# Fuente.net
KiCad netlist of a schematic drawn in Altium Designer
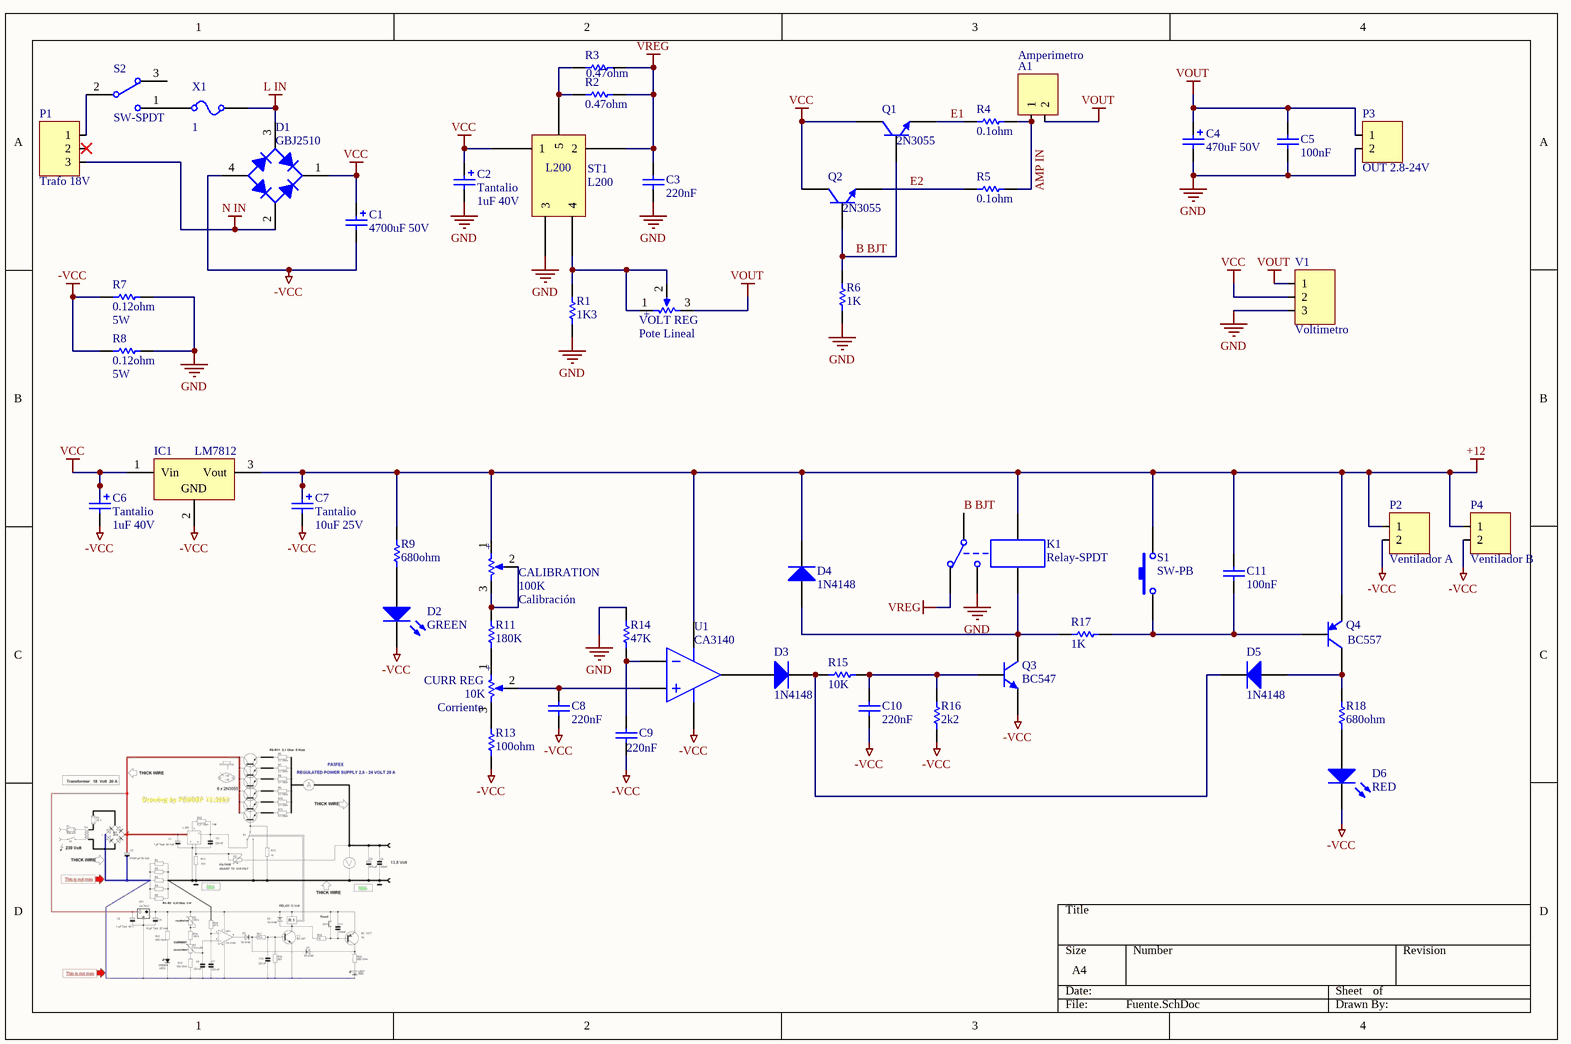
[diagram p0: Fuente.SchDoc]

(export (version "E")
  (design (tool "Eeschema 10.0.6"))
  (components
    (comp (ref "A1")
      (value "Amperimetro")
      (footprint "BORNERA 2")
      (description "Header, 2-Pin")
      (fields (field (name "PUBLISHER") "Altium Limited"))
      (libsource (lib "SchLibPutallaz") (part "Bornera"))
    )
    (comp (ref "C1")
      (value "4700uF 50V")
      (footprint "CAP 20MM")
      (description "Polarized Capacitor (Radial)")
      (fields (field (name "PUBLISHER") "Altium Limited"))
      (libsource (lib "SchLibPutallaz") (part "Cap Pol1"))
    )
    (comp (ref "C2")
      (value "Tantalio")
      (footprint "Cap Tantalio")
      (description "Polarized Capacitor (Radial)")
      (fields (field (name "ALTIUM_VALUE") "1uF 40V") (field (name "PUBLISHER") "Altium Limited"))
      (libsource (lib "SchLibPutallaz") (part "Cap Pol1"))
    )
    (comp (ref "C3")
      (value "220nF")
      (footprint "1206 res")
      (description "Capacitor")
      (fields (field (name "PUBLISHER") "Altium Limited"))
      (libsource (lib "SchLibPutallaz") (part "Cap"))
    )
    (comp (ref "C4")
      (value "470uF 50V")
      (footprint "CAP 10mm")
      (description "Polarized Capacitor (Radial)")
      (fields (field (name "PUBLISHER") "Altium Limited"))
      (libsource (lib "SchLibPutallaz") (part "Cap Pol1"))
    )
    (comp (ref "C5")
      (value "100nF")
      (footprint "0805 res")
      (description "Capacitor")
      (fields (field (name "PUBLISHER") "Altium Limited"))
      (libsource (lib "SchLibPutallaz") (part "Cap"))
    )
    (comp (ref "C6")
      (value "Tantalio")
      (footprint "Cap Tantalio")
      (description "Polarized Capacitor (Radial)")
      (fields (field (name "ALTIUM_VALUE") "1uF 40V") (field (name "PUBLISHER") "Altium Limited"))
      (libsource (lib "SchLibPutallaz") (part "Cap Pol1"))
    )
    (comp (ref "C7")
      (value "Tantalio")
      (footprint "Cap Tantalio")
      (description "Polarized Capacitor (Radial)")
      (fields (field (name "ALTIUM_VALUE") "10uF 25V") (field (name "PUBLISHER") "Altium Limited"))
      (libsource (lib "SchLibPutallaz") (part "Cap Pol1"))
    )
    (comp (ref "C8")
      (value "220nF")
      (footprint "1206 res")
      (description "Capacitor")
      (fields (field (name "PUBLISHER") "Altium Limited"))
      (libsource (lib "SchLibPutallaz") (part "Cap"))
    )
    (comp (ref "C9")
      (value "220nF")
      (footprint "1206 res")
      (description "Capacitor")
      (fields (field (name "PUBLISHER") "Altium Limited"))
      (libsource (lib "SchLibPutallaz") (part "Cap"))
    )
    (comp (ref "C10")
      (value "220nF")
      (footprint "1206 res")
      (description "Capacitor")
      (fields (field (name "PUBLISHER") "Altium Limited"))
      (libsource (lib "SchLibPutallaz") (part "Cap"))
    )
    (comp (ref "C11")
      (value "100nF")
      (footprint "0805 res")
      (description "Capacitor")
      (fields (field (name "PUBLISHER") "Altium Limited"))
      (libsource (lib "SchLibPutallaz") (part "Cap"))
    )
    (comp (ref "CALIBRATION")
      (value "100K")
      (footprint "Potenciometro")
      (libsource (lib "SchLibPutallaz") (part "Potenciometro"))
    )
    (comp (ref "CURR REG")
      (value "10K")
      (footprint "Potenciometro")
      (libsource (lib "SchLibPutallaz") (part "Potenciometro"))
    )
    (comp (ref "D1")
      (value "GBJ2510")
      (footprint "DIOB_GBJ2510")
      (description "Full Wave Diode Bridge")
      (fields (field (name "PUBLISHER") "Altium Limited"))
      (libsource (lib "SchLibPutallaz") (part "Bridge1"))
    )
    (comp (ref "D2")
      (value "GREEN")
      (footprint "LED 5MM GREEN")
      (description "Typical BLUE SiC LED")
      (fields (field (name "PUBLISHER") "Altium Limited"))
      (libsource (lib "SchLibPutallaz") (part "LED5"))
    )
    (comp (ref "D3")
      (value "1N4148")
      (footprint "DO-38")
      (description "1 Amp General Purpose Rectifier")
      (fields (field (name "PUBLISHER") "Altium Limited"))
      (libsource (lib "SchLibPutallaz") (part "Diode 1N4007"))
    )
    (comp (ref "D4")
      (value "1N4148")
      (footprint "DO-38")
      (description "1 Amp General Purpose Rectifier")
      (fields (field (name "PUBLISHER") "Altium Limited"))
      (libsource (lib "SchLibPutallaz") (part "Diode 1N4007"))
    )
    (comp (ref "D5")
      (value "1N4148")
      (footprint "DO-38")
      (description "1 Amp General Purpose Rectifier")
      (fields (field (name "PUBLISHER") "Altium Limited"))
      (libsource (lib "SchLibPutallaz") (part "Diode 1N4007"))
    )
    (comp (ref "D6")
      (value "RED")
      (footprint "LED 5MM")
      (description "Typical BLUE SiC LED")
      (fields (field (name "PUBLISHER") "Altium Limited"))
      (libsource (lib "SchLibPutallaz") (part "LED5"))
    )
    (comp (ref "IC1") (value "LM7812") (footprint "TO220") (libsource (lib "SchLibPutallaz") (part "LM7812")))
    (comp (ref "K1")
      (value "Relay-SPDT")
      (footprint "Relay")
      (description "Single-Pole Dual-Throw Relay")
      (fields (field (name "PUBLISHER") "Altium Limited"))
      (libsource (lib "SchLibPutallaz") (part "Relay-SPDT"))
    )
    (comp (ref "P1")
      (value "Trafo 18V")
      (footprint "Bornera 3")
      (description "Header, 3-Pin")
      (fields (field (name "PUBLISHER") "Altium Limited"))
      (libsource (lib "SchLibPutallaz") (part "Bornera 3pin"))
    )
    (comp (ref "P2")
      (value "Ventilador A")
      (footprint "HDR1X2")
      (description "Header, 2-Pin")
      (fields (field (name "PUBLISHER") "Altium Limited"))
      (libsource (lib "SchLibPutallaz") (part "Header 2"))
    )
    (comp (ref "P3")
      (value "OUT 2.8-24V")
      (footprint "BORNERA 2")
      (description "Header, 2-Pin")
      (fields (field (name "PUBLISHER") "Altium Limited"))
      (libsource (lib "") (part "Bornera_1"))
    )
    (comp (ref "P4")
      (value "Ventilador B")
      (footprint "HDR1X2")
      (description "Header, 2-Pin")
      (fields (field (name "PUBLISHER") "Altium Limited"))
      (libsource (lib "SchLibPutallaz") (part "Header 2"))
    )
    (comp (ref "Q1")
      (value "2N3055")
      (footprint "Bornera 3")
      (description "NPN General Purpose Amplifier")
      (fields (field (name "PUBLISHER") "Altium Limited"))
      (libsource (lib "") (part "BC547_1"))
    )
    (comp (ref "Q2")
      (value "2N3055")
      (footprint "Bornera 3")
      (description "NPN General Purpose Amplifier")
      (fields (field (name "PUBLISHER") "Altium Limited"))
      (libsource (lib "SchLibPutallaz") (part "BC547"))
    )
    (comp (ref "Q3")
      (value "BC547")
      (footprint "TO-92A")
      (description "NPN General Purpose Amplifier")
      (fields (field (name "PUBLISHER") "Altium Limited"))
      (libsource (lib "SchLibPutallaz") (part "BC547"))
    )
    (comp (ref "Q4")
      (value "BC557")
      (footprint "TO-92A")
      (description "Bipolar PNP 3 Pins Transistor Gummel-Poon Model")
      (libsource (lib "SchLibPutallaz") (part "BJT PNP GP"))
    )
    (comp (ref "R1")
      (value "1K3")
      (footprint "1206 res")
      (description "Resistor")
      (fields (field (name "PUBLISHER") "Altium Limited"))
      (libsource (lib "SchLibPutallaz") (part "Res1"))
    )
    (comp (ref "R2")
      (value "0.47ohm")
      (footprint "Res Axial 0.5")
      (description "Resistor")
      (fields (field (name "PUBLISHER") "Altium Limited"))
      (libsource (lib "SchLibPutallaz") (part "Res1"))
    )
    (comp (ref "R3")
      (value "0.47ohm")
      (footprint "Res Axial 0.5")
      (description "Resistor")
      (fields (field (name "PUBLISHER") "Altium Limited"))
      (libsource (lib "SchLibPutallaz") (part "Res1"))
    )
    (comp (ref "R4")
      (value "0.1ohm")
      (footprint "RES AXIAL 5W")
      (description "Resistor")
      (fields (field (name "PUBLISHER") "Altium Limited"))
      (libsource (lib "SchLibPutallaz") (part "Res1"))
    )
    (comp (ref "R5")
      (value "0.1ohm")
      (footprint "RES AXIAL 5W")
      (description "Resistor")
      (fields (field (name "PUBLISHER") "Altium Limited"))
      (libsource (lib "SchLibPutallaz") (part "Res1"))
    )
    (comp (ref "R6")
      (value "1K")
      (footprint "1206 res")
      (description "Resistor")
      (fields (field (name "PUBLISHER") "Altium Limited"))
      (libsource (lib "SchLibPutallaz") (part "Res1"))
    )
    (comp (ref "R7")
      (value "0.12ohm")
      (footprint "RES AXIAL 5W")
      (description "Resistor")
      (fields (field (name "ALTIUM_VALUE") "5W") (field (name "PUBLISHER") "Altium Limited"))
      (libsource (lib "SchLibPutallaz") (part "Res1"))
    )
    (comp (ref "R8")
      (value "0.12ohm")
      (footprint "RES AXIAL 5W")
      (description "Resistor")
      (fields (field (name "ALTIUM_VALUE") "5W") (field (name "PUBLISHER") "Altium Limited"))
      (libsource (lib "SchLibPutallaz") (part "Res1"))
    )
    (comp (ref "R9")
      (value "680ohm")
      (footprint "1206 res")
      (description "Resistor")
      (fields (field (name "PUBLISHER") "Altium Limited"))
      (libsource (lib "SchLibPutallaz") (part "Res1"))
    )
    (comp (ref "R11")
      (value "180K")
      (footprint "1206 res")
      (description "Resistor")
      (fields (field (name "PUBLISHER") "Altium Limited"))
      (libsource (lib "SchLibPutallaz") (part "Res1"))
    )
    (comp (ref "R13")
      (value "100ohm")
      (footprint "1206 res")
      (description "Resistor")
      (fields (field (name "PUBLISHER") "Altium Limited"))
      (libsource (lib "SchLibPutallaz") (part "Res1"))
    )
    (comp (ref "R14")
      (value "47K")
      (footprint "1206 res")
      (description "Resistor")
      (fields (field (name "PUBLISHER") "Altium Limited"))
      (libsource (lib "SchLibPutallaz") (part "Res1"))
    )
    (comp (ref "R15")
      (value "10K")
      (footprint "1206 res")
      (description "Resistor")
      (fields (field (name "PUBLISHER") "Altium Limited"))
      (libsource (lib "SchLibPutallaz") (part "Res1"))
    )
    (comp (ref "R16")
      (value "2k2")
      (footprint "1206 res")
      (description "Resistor")
      (fields (field (name "PUBLISHER") "Altium Limited"))
      (libsource (lib "SchLibPutallaz") (part "Res1"))
    )
    (comp (ref "R17")
      (value "1K")
      (footprint "1206 res")
      (description "Resistor")
      (fields (field (name "PUBLISHER") "Altium Limited"))
      (libsource (lib "SchLibPutallaz") (part "Res1"))
    )
    (comp (ref "R18")
      (value "680ohm")
      (footprint "1206 res")
      (description "Resistor")
      (fields (field (name "PUBLISHER") "Altium Limited"))
      (libsource (lib "SchLibPutallaz") (part "Res1"))
    )
    (comp (ref "S1")
      (value "SW-PB")
      (footprint "Pulsador")
      (description "Switch")
      (fields (field (name "PUBLISHER") "Altium Limited"))
      (libsource (lib "SchLibPutallaz") (part "SW-PNA"))
    )
    (comp (ref "S2")
      (value "SW-SPDT")
      (footprint "Bornera 3")
      (description "SPDT Subminiature Toggle Switch, Right Angle Mounting, Vertical Actuation")
      (fields (field (name "PUBLISHER") "Altium Limited"))
      (libsource (lib "SchLibPutallaz") (part "SW-SPDT"))
    )
    (comp (ref "ST1") (value "L200") (footprint "PENTAWATT") (libsource (lib "Fuente") (part "L200")))
    (comp (ref "U1")
      (value "Amplificador Operacional")
      (footprint "DIP8")
      (description "Ideal Operational Amplifier")
      (libsource (lib "SchLibPutallaz") (part "OpAmp with power terminals"))
    )
    (comp (ref "V1")
      (value "Voltimetro")
      (footprint "HDR1X3")
      (description "Header, 3-Pin")
      (fields (field (name "PUBLISHER") "Altium Limited"))
      (libsource (lib "SchLibPutallaz") (part "Header 3"))
    )
    (comp (ref "VOLT REG")
      (value "Pote Lineal")
      (footprint "Potenciometro")
      (libsource (lib "SchLibPutallaz") (part "Potenciometro"))
    )
    (comp (ref "X1")
      (value "Fuse")
      (footprint "Fusiblera")
      (fields (field (name "CURRENT") "1"))
      (libsource (lib "Fuente") (part "Fuse_1"))
    )
  )
  (nets
    (net (code "1") (name "+12") (class "Default")
      (node (ref "C11") (pin "2") (pinfunction "2_2") (pintype "passive"))
      (node (ref "C7") (pin "1") (pinfunction "1_1") (pintype "passive"))
      (node (ref "CALIBRATION") (pin "1") (pinfunction "TOP_1") (pintype "passive"))
      (node (ref "D4") (pin "2") (pinfunction "K_2") (pintype "passive"))
      (node (ref "IC1") (pin "3") (pinfunction "Vout_3") (pintype "passive"))
      (node (ref "K1") (pin "1") (pinfunction "1_1") (pintype "passive"))
      (node (ref "P2") (pin "1") (pinfunction "1_1") (pintype "passive"))
      (node (ref "P4") (pin "1") (pinfunction "1_1") (pintype "passive"))
      (node (ref "Q4") (pin "3") (pinfunction "E_3") (pintype "passive"))
      (node (ref "R9") (pin "2") (pinfunction "2_2") (pintype "passive"))
      (node (ref "S1") (pin "2") (pinfunction "2_2") (pintype "passive"))
      (node (ref "U1") (pin "7") (pinfunction "V+_7") (pintype "power_in"))
    )
    (net (code "2") (name "-VCC") (class "Default")
      (node (ref "C1") (pin "2") (pinfunction "2_2") (pintype "passive"))
      (node (ref "C10") (pin "1") (pinfunction "1_1") (pintype "passive"))
      (node (ref "C6") (pin "2") (pinfunction "2_2") (pintype "passive"))
      (node (ref "C7") (pin "2") (pinfunction "2_2") (pintype "passive"))
      (node (ref "C8") (pin "1") (pinfunction "1_1") (pintype "passive"))
      (node (ref "C9") (pin "1") (pinfunction "1_1") (pintype "passive"))
      (node (ref "D1") (pin "4") (pinfunction "A_4") (pintype "passive"))
      (node (ref "D2") (pin "2") (pinfunction "K_2") (pintype "passive"))
      (node (ref "D6") (pin "2") (pinfunction "K_2") (pintype "passive"))
      (node (ref "IC1") (pin "2") (pinfunction "GND_2") (pintype "passive"))
      (node (ref "P2") (pin "2") (pinfunction "2_2") (pintype "passive"))
      (node (ref "P4") (pin "2") (pinfunction "2_2") (pintype "passive"))
      (node (ref "Q3") (pin "3") (pinfunction "E_3") (pintype "passive"))
      (node (ref "R13") (pin "1") (pinfunction "1_1") (pintype "passive"))
      (node (ref "R16") (pin "1") (pinfunction "1_1") (pintype "passive"))
      (node (ref "R7") (pin "1") (pinfunction "1_1") (pintype "passive"))
      (node (ref "R8") (pin "1") (pinfunction "1_1") (pintype "passive"))
      (node (ref "U1") (pin "4") (pinfunction "V-_4") (pintype "power_in"))
    )
    (net (code "3") (name "/AMP IN") (class "Default")
      (node (ref "A1") (pin "1") (pinfunction "1_1") (pintype "passive"))
      (node (ref "R4") (pin "2") (pinfunction "2_2") (pintype "passive"))
      (node (ref "R5") (pin "2") (pinfunction "2_2") (pintype "passive"))
    )
    (net (code "4") (name "/B BJT") (class "Default")
      (node (ref "K1") (pin "3") (pinfunction "3_3") (pintype "passive"))
      (node (ref "Q1") (pin "2") (pinfunction "B_2") (pintype "passive"))
      (node (ref "Q2") (pin "2") (pinfunction "B_2") (pintype "passive"))
      (node (ref "R6") (pin "2") (pinfunction "2_2") (pintype "passive"))
    )
    (net (code "5") (name "/E1") (class "Default")
      (node (ref "Q1") (pin "1") (pinfunction "E_1") (pintype "passive"))
      (node (ref "R4") (pin "1") (pinfunction "1_1") (pintype "passive"))
    )
    (net (code "6") (name "/E2") (class "Default")
      (node (ref "Q2") (pin "3") (pinfunction "E_3") (pintype "passive"))
      (node (ref "R5") (pin "1") (pinfunction "1_1") (pintype "passive"))
    )
    (net (code "7") (name "GND") (class "Default")
      (node (ref "C2") (pin "2") (pinfunction "2_2") (pintype "passive"))
      (node (ref "C3") (pin "1") (pinfunction "1_1") (pintype "passive"))
      (node (ref "C4") (pin "2") (pinfunction "2_2") (pintype "passive"))
      (node (ref "C5") (pin "1") (pinfunction "1_1") (pintype "passive"))
      (node (ref "K1") (pin "5") (pinfunction "5_5") (pintype "passive"))
      (node (ref "P3") (pin "1") (pinfunction "2_1") (pintype "passive"))
      (node (ref "R1") (pin "1") (pinfunction "1_1") (pintype "passive"))
      (node (ref "R14") (pin "2") (pinfunction "2_2") (pintype "passive"))
      (node (ref "R6") (pin "1") (pinfunction "1_1") (pintype "passive"))
      (node (ref "R7") (pin "2") (pinfunction "2_2") (pintype "passive"))
      (node (ref "R8") (pin "2") (pinfunction "2_2") (pintype "passive"))
      (node (ref "ST1") (pin "3") (pinfunction "3_3") (pintype "passive"))
      (node (ref "V1") (pin "3") (pinfunction "3_3") (pintype "passive"))
    )
    (net (code "8") (name "L IN") (class "Default")
      (node (ref "D1") (pin "3") (pinfunction "C_3") (pintype "passive"))
      (node (ref "X1") (pin "2") (pinfunction "2_2") (pintype "passive"))
    )
    (net (code "9") (name "N IN") (class "Default")
      (node (ref "D1") (pin "2") (pinfunction "C_2") (pintype "passive"))
      (node (ref "P1") (pin "3") (pinfunction "3_3") (pintype "passive"))
    )
    (net (code "10") (name "Net-(CALIBRATION-BOTTOM)") (class "Default")
      (node (ref "CALIBRATION") (pin "2") (pinfunction "TAP_2") (pintype "passive"))
      (node (ref "CALIBRATION") (pin "3") (pinfunction "BOTTOM_3") (pintype "passive"))
      (node (ref "R11") (pin "2") (pinfunction "2_2") (pintype "passive"))
    )
    (net (code "11") (name "Net-(CURR REG-BOTTOM)") (class "Default")
      (node (ref "CURR REG") (pin "3") (pinfunction "BOTTOM_3") (pintype "passive"))
      (node (ref "R13") (pin "2") (pinfunction "2_2") (pintype "passive"))
    )
    (net (code "12") (name "Net-(CURR REG-TAP)") (class "Default")
      (node (ref "C8") (pin "2") (pinfunction "2_2") (pintype "passive"))
      (node (ref "CURR REG") (pin "2") (pinfunction "TAP_2") (pintype "passive"))
      (node (ref "U1") (pin "3") (pinfunction "IN+_3") (pintype "passive"))
    )
    (net (code "13") (name "Net-(CURR REG-TOP)") (class "Default")
      (node (ref "CURR REG") (pin "1") (pinfunction "TOP_1") (pintype "passive"))
      (node (ref "R11") (pin "1") (pinfunction "1_1") (pintype "passive"))
    )
    (net (code "14") (name "Net-(D2-A)") (class "Default")
      (node (ref "D2") (pin "1") (pinfunction "A_1") (pintype "passive"))
      (node (ref "R9") (pin "1") (pinfunction "1_1") (pintype "passive"))
    )
    (net (code "15") (name "Net-(D3-A)") (class "Default")
      (node (ref "D3") (pin "1") (pinfunction "A_1") (pintype "passive"))
      (node (ref "U1") (pin "6") (pinfunction "OUT_6") (pintype "passive"))
    )
    (net (code "16") (name "Net-(D3-K)") (class "Default")
      (node (ref "D3") (pin "2") (pinfunction "K_2") (pintype "passive"))
      (node (ref "D5") (pin "2") (pinfunction "K_2") (pintype "passive"))
      (node (ref "R15") (pin "1") (pinfunction "1_1") (pintype "passive"))
    )
    (net (code "17") (name "Net-(D4-A)") (class "Default")
      (node (ref "D4") (pin "1") (pinfunction "A_1") (pintype "passive"))
      (node (ref "K1") (pin "2") (pinfunction "2_2") (pintype "passive"))
      (node (ref "Q3") (pin "1") (pinfunction "C_1") (pintype "passive"))
      (node (ref "R17") (pin "1") (pinfunction "1_1") (pintype "passive"))
    )
    (net (code "18") (name "Net-(D5-A)") (class "Default")
      (node (ref "D5") (pin "1") (pinfunction "A_1") (pintype "passive"))
      (node (ref "Q4") (pin "1") (pinfunction "C_1") (pintype "passive"))
      (node (ref "R18") (pin "2") (pinfunction "2_2") (pintype "passive"))
    )
    (net (code "19") (name "Net-(D6-A)") (class "Default")
      (node (ref "D6") (pin "1") (pinfunction "A_1") (pintype "passive"))
      (node (ref "R18") (pin "1") (pinfunction "1_1") (pintype "passive"))
    )
    (net (code "20") (name "Net-(Q3-B)") (class "Default")
      (node (ref "C10") (pin "2") (pinfunction "2_2") (pintype "passive"))
      (node (ref "Q3") (pin "2") (pinfunction "B_2") (pintype "passive"))
      (node (ref "R15") (pin "2") (pinfunction "2_2") (pintype "passive"))
      (node (ref "R16") (pin "2") (pinfunction "2_2") (pintype "passive"))
    )
    (net (code "21") (name "Net-(Q4-B)") (class "Default")
      (node (ref "C11") (pin "1") (pinfunction "1_1") (pintype "passive"))
      (node (ref "Q4") (pin "2") (pinfunction "B_2") (pintype "passive"))
      (node (ref "R17") (pin "2") (pinfunction "2_2") (pintype "passive"))
      (node (ref "S1") (pin "1") (pinfunction "1_1") (pintype "passive"))
    )
    (net (code "22") (name "Net-(R2-Pad1)") (class "Default")
      (node (ref "R2") (pin "1") (pinfunction "1_1") (pintype "passive"))
      (node (ref "R3") (pin "1") (pinfunction "1_1") (pintype "passive"))
      (node (ref "ST1") (pin "5") (pinfunction "5_5") (pintype "passive"))
    )
    (net (code "23") (name "Net-(S2-1)") (class "Default")
      (node (ref "P1") (pin "1") (pinfunction "1_1") (pintype "passive"))
      (node (ref "S2") (pin "2") (pinfunction "1_2") (pintype "passive"))
    )
    (net (code "24") (name "Net-(S2-2)") (class "Default")
      (node (ref "S2") (pin "1") (pinfunction "2_1") (pintype "passive"))
      (node (ref "X1") (pin "1") (pinfunction "1_1") (pintype "passive"))
    )
    (net (code "25") (name "Net-(U1-IN-)") (class "Default")
      (node (ref "C9") (pin "2") (pinfunction "2_2") (pintype "passive"))
      (node (ref "R14") (pin "1") (pinfunction "1_1") (pintype "passive"))
      (node (ref "U1") (pin "2") (pinfunction "IN-_2") (pintype "passive"))
    )
    (net (code "26") (name "Net-(VOLT REG-TAP)") (class "Default")
      (node (ref "R1") (pin "2") (pinfunction "2_2") (pintype "passive"))
      (node (ref "ST1") (pin "4") (pinfunction "4_4") (pintype "passive"))
      (node (ref "VOLT REG") (pin "1") (pinfunction "TOP_1") (pintype "passive"))
      (node (ref "VOLT REG") (pin "2") (pinfunction "TAP_2") (pintype "passive"))
    )
    (net (code "27") (name "VCC") (class "Default")
      (node (ref "C1") (pin "1") (pinfunction "1_1") (pintype "passive"))
      (node (ref "C2") (pin "1") (pinfunction "1_1") (pintype "passive"))
      (node (ref "C6") (pin "1") (pinfunction "1_1") (pintype "passive"))
      (node (ref "D1") (pin "1") (pinfunction "K_1") (pintype "passive"))
      (node (ref "IC1") (pin "1") (pinfunction "Vin_1") (pintype "passive"))
      (node (ref "Q1") (pin "3") (pinfunction "C_3") (pintype "passive"))
      (node (ref "Q2") (pin "1") (pinfunction "C_1") (pintype "passive"))
      (node (ref "ST1") (pin "1") (pinfunction "1_1") (pintype "passive"))
      (node (ref "V1") (pin "2") (pinfunction "2_2") (pintype "passive"))
    )
    (net (code "28") (name "VOUT") (class "Default")
      (node (ref "A1") (pin "2") (pinfunction "2_2") (pintype "passive"))
      (node (ref "C4") (pin "1") (pinfunction "1_1") (pintype "passive"))
      (node (ref "C5") (pin "2") (pinfunction "2_2") (pintype "passive"))
      (node (ref "P3") (pin "2") (pinfunction "1_2") (pintype "passive"))
      (node (ref "V1") (pin "1") (pinfunction "1_1") (pintype "passive"))
      (node (ref "VOLT REG") (pin "3") (pinfunction "BOTTOM_3") (pintype "passive"))
    )
    (net (code "29") (name "VREG") (class "Default")
      (node (ref "C3") (pin "2") (pinfunction "2_2") (pintype "passive"))
      (node (ref "K1") (pin "4") (pinfunction "4_4") (pintype "passive"))
      (node (ref "R2") (pin "2") (pinfunction "2_2") (pintype "passive"))
      (node (ref "R3") (pin "2") (pinfunction "2_2") (pintype "passive"))
      (node (ref "ST1") (pin "2") (pinfunction "2_2") (pintype "passive"))
    )
    (net (code "30") (name "unconnected-(P1-Pad2)") (class "Default")
      (node (ref "P1") (pin "2") (pinfunction "2_2") (pintype "passive+no_connect"))
    )
    (net (code "31") (name "unconnected-(S2-Pad3)") (class "Default")
      (node (ref "S2") (pin "3") (pinfunction "3_3") (pintype "passive"))
    )
  )
)
